# ADC.net
KiCad netlist of a schematic drawn in Altium Designer
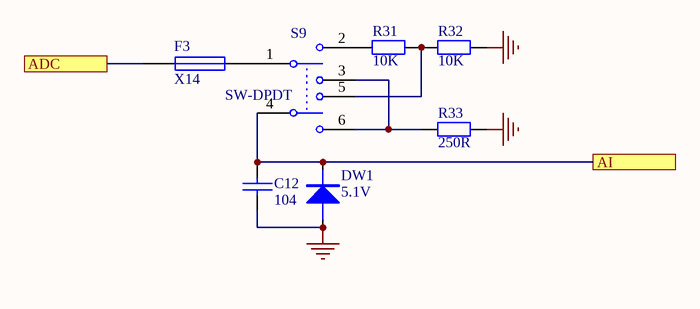
[diagram p0: ADC.SchDoc]

(export (version "E")
  (design (tool "Eeschema 10.0.6"))
  (components
    (comp (ref "C12")
      (value "104")
      (footprint "C0805C")
      (description "Capacitor")
      (libsource (lib "*") (part "CAP"))
    )
    (comp (ref "DW1")
      (value "5.1V")
      (footprint "1206AK")
      (description "Diode")
      (libsource (lib "*") (part "DIODE"))
    )
    (comp (ref "F3")
      (value "X14")
      (footprint "PPTC_SMT")
      (description "Fuse")
      (fields (field (name "PUBLISHER") "Altium Limited"))
      (libsource (lib "Miscellaneous Devices") (part "Fuse 1"))
    )
    (comp (ref "R31")
      (value "10K")
      (footprint "0805R")
      (description "Resistor")
      (fields (field (name "PUBLISHER") "Altium Limited"))
      (libsource (lib "Miscellaneous Devices") (part "res"))
    )
    (comp (ref "R32")
      (value "10K")
      (footprint "0805R")
      (description "Resistor")
      (fields (field (name "PUBLISHER") "Altium Limited"))
      (libsource (lib "Miscellaneous Devices") (part "res"))
    )
    (comp (ref "R33")
      (value "250R")
      (footprint "0805R")
      (description "Resistor")
      (fields (field (name "PUBLISHER") "Altium Limited"))
      (libsource (lib "Miscellaneous Devices") (part "res"))
    )
    (comp (ref "S9")
      (value "SW-DPDT")
      (footprint "button")
      (description "Double-Pole, Double-Throw Switch")
      (fields (field (name "PUBLISHER") "Altium Limited"))
      (libsource (lib "Miscellaneous Devices") (part "SW-DPDT"))
    )
  )
  (nets
    (net (code "1") (name "/ADC") (class "Default")
      (node (ref "F3") (pin "1") (pinfunction "1_1") (pintype "passive"))
    )
    (net (code "2") (name "/AI") (class "Default")
      (node (ref "C12") (pin "1") (pinfunction "1_1") (pintype "passive"))
      (node (ref "DW1") (pin "K") (pinfunction "K_K") (pintype "passive"))
      (node (ref "S9") (pin "4") (pinfunction "4_4") (pintype "passive"))
    )
    (net (code "3") (name "GND") (class "Default")
      (node (ref "C12") (pin "2") (pinfunction "2_2") (pintype "passive"))
      (node (ref "DW1") (pin "A") (pinfunction "A_A") (pintype "passive"))
      (node (ref "R32") (pin "2") (pinfunction "2_2") (pintype "passive"))
      (node (ref "R33") (pin "2") (pinfunction "2_2") (pintype "passive"))
    )
    (net (code "4") (name "Net-(F3-Pad2)") (class "Default")
      (node (ref "F3") (pin "2") (pinfunction "2_2") (pintype "passive"))
      (node (ref "S9") (pin "1") (pinfunction "1_1") (pintype "passive"))
    )
    (net (code "5") (name "Net-(R31-Pad1)") (class "Default")
      (node (ref "R31") (pin "1") (pinfunction "1_1") (pintype "passive"))
      (node (ref "S9") (pin "2") (pinfunction "2_2") (pintype "passive"))
    )
    (net (code "6") (name "Net-(R31-Pad2)") (class "Default")
      (node (ref "R31") (pin "2") (pinfunction "2_2") (pintype "passive"))
      (node (ref "R32") (pin "1") (pinfunction "1_1") (pintype "passive"))
      (node (ref "S9") (pin "5") (pinfunction "5_5") (pintype "passive"))
    )
    (net (code "7") (name "Net-(R33-Pad1)") (class "Default")
      (node (ref "R33") (pin "1") (pinfunction "1_1") (pintype "passive"))
      (node (ref "S9") (pin "3") (pinfunction "3_3") (pintype "passive"))
      (node (ref "S9") (pin "6") (pinfunction "6_6") (pintype "passive"))
    )
  )
)
